# LPCB280_-_POWER.net
KiCad netlist of a schematic drawn in Altium Designer
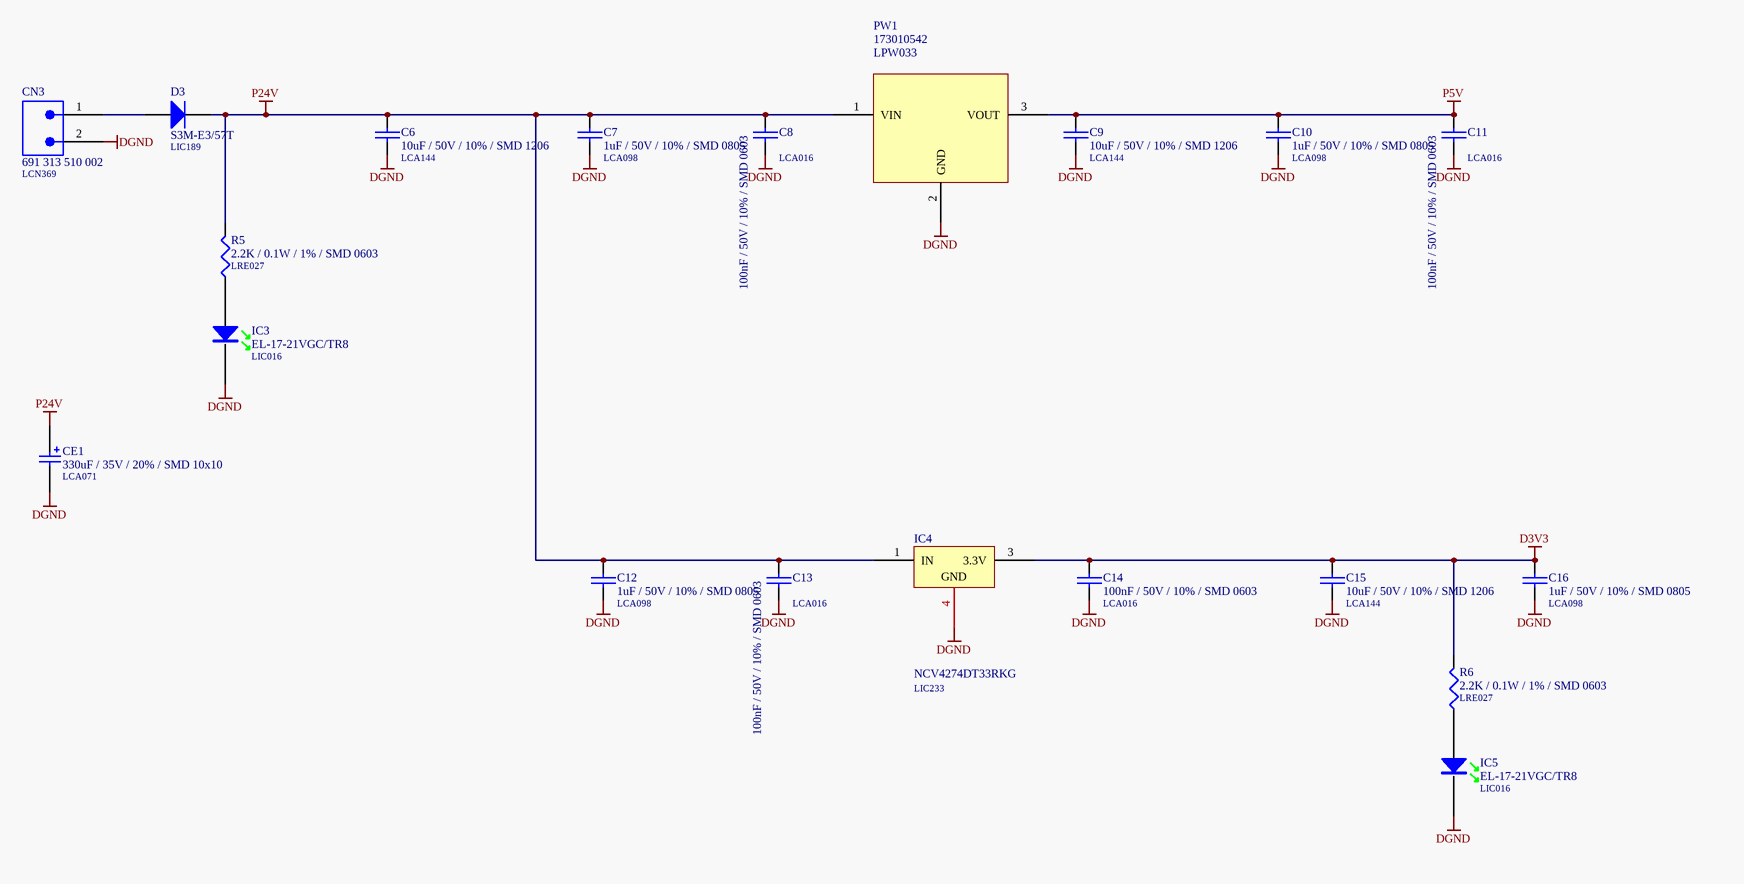
[diagram p0: LPCB280 - POWER.SchDoc]

(export (version "E")
  (design (tool "Eeschema 10.0.6"))
  (components
    (comp (ref "C6")
      (value "10uF / 50V / 10% / SMD 1206")
      (footprint "LFP043__CC3216-1206")
      (description "Capacitor, Ceramic Chip, 10uF, 50V, X5R, 10%, SMD 1206 [LCA144]")
      (fields (field (name "LDL_NUMBER") "LCA144"))
      (libsource (lib "LDL_Capacitors") (part "10uF / 50V / 10% / SMD 1206"))
    )
    (comp (ref "C7")
      (value "1uF / 50V / 10% / SMD 0805")
      (footprint "LFP010__CC2012-0805-IPC7351_B")
      (description "Capacitor, Ceramic Chip, 1uF, 50V, SMD 0805 [LCA098]")
      (fields (field (name "LDL_NUMBER") "LCA098"))
      (libsource (lib "LDL_Capacitors") (part "1uF / 50V / 10% / SMD 0805"))
    )
    (comp (ref "C8")
      (value "100nF / 50V / 10% / SMD 0603")
      (footprint "LFP011__CC1608-0603-IPC7351_B")
      (description "Capacitor, Ceramic Chip, 100nF (0.1uF), 50V, 5%, SMD 0603 [LCA016]")
      (fields (field (name "LDL_NUMBER") "LCA016"))
      (libsource (lib "LDL_Capacitors") (part "100nF / 50V / 10% / SMD 0603"))
    )
    (comp (ref "C9")
      (value "10uF / 50V / 10% / SMD 1206")
      (footprint "LFP043__CC3216-1206")
      (description "Capacitor, Ceramic Chip, 10uF, 50V, X5R, 10%, SMD 1206 [LCA144]")
      (fields (field (name "LDL_NUMBER") "LCA144"))
      (libsource (lib "LDL_Capacitors") (part "10uF / 50V / 10% / SMD 1206"))
    )
    (comp (ref "C10")
      (value "1uF / 50V / 10% / SMD 0805")
      (footprint "LFP010__CC2012-0805-IPC7351_B")
      (description "Capacitor, Ceramic Chip, 1uF, 50V, SMD 0805 [LCA098]")
      (fields (field (name "LDL_NUMBER") "LCA098"))
      (libsource (lib "LDL_Capacitors") (part "1uF / 50V / 10% / SMD 0805"))
    )
    (comp (ref "C11")
      (value "100nF / 50V / 10% / SMD 0603")
      (footprint "LFP011__CC1608-0603-IPC7351_B")
      (description "Capacitor, Ceramic Chip, 100nF (0.1uF), 50V, 5%, SMD 0603 [LCA016]")
      (fields (field (name "LDL_NUMBER") "LCA016"))
      (libsource (lib "LDL_Capacitors") (part "100nF / 50V / 10% / SMD 0603"))
    )
    (comp (ref "C12")
      (value "1uF / 50V / 10% / SMD 0805")
      (footprint "LFP010__CC2012-0805-IPC7351_B")
      (description "Capacitor, Ceramic Chip, 1uF, 50V, SMD 0805 [LCA098]")
      (fields (field (name "LDL_NUMBER") "LCA098"))
      (libsource (lib "LDL_Capacitors") (part "1uF / 50V / 10% / SMD 0805"))
    )
    (comp (ref "C13")
      (value "100nF / 50V / 10% / SMD 0603")
      (footprint "LFP011__CC1608-0603-IPC7351_B")
      (description "Capacitor, Ceramic Chip, 100nF (0.1uF), 50V, 5%, SMD 0603 [LCA016]")
      (fields (field (name "LDL_NUMBER") "LCA016"))
      (libsource (lib "LDL_Capacitors") (part "100nF / 50V / 10% / SMD 0603"))
    )
    (comp (ref "C14")
      (value "100nF / 50V / 10% / SMD 0603")
      (footprint "LFP011__CC1608-0603-IPC7351_B")
      (description "Capacitor, Ceramic Chip, 100nF (0.1uF), 50V, 5%, SMD 0603 [LCA016]")
      (fields (field (name "LDL_NUMBER") "LCA016"))
      (libsource (lib "LDL_Capacitors") (part "100nF / 50V / 10% / SMD 0603"))
    )
    (comp (ref "C15")
      (value "10uF / 50V / 10% / SMD 1206")
      (footprint "LFP043__CC3216-1206")
      (description "Capacitor, Ceramic Chip, 10uF, 50V, X5R, 10%, SMD 1206 [LCA144]")
      (fields (field (name "LDL_NUMBER") "LCA144"))
      (libsource (lib "LDL_Capacitors") (part "10uF / 50V / 10% / SMD 1206"))
    )
    (comp (ref "C16")
      (value "1uF / 50V / 10% / SMD 0805")
      (footprint "LFP010__CC2012-0805-IPC7351_B")
      (description "Capacitor, Ceramic Chip, 1uF, 50V, SMD 0805 [LCA098]")
      (fields (field (name "LDL_NUMBER") "LCA098"))
      (libsource (lib "LDL_Capacitors") (part "1uF / 50V / 10% / SMD 0805"))
    )
    (comp (ref "CE1")
      (value "330uF / 35V / 20% / SMD 10x10")
      (footprint "LFP041__NICHICON_WT_10X10")
      (description "Capacitor, Aluminum Electrolytic, 330uF, 35V, 20%, SMD (10mm x 10mm) [LCA071]")
      (fields (field (name "LDL_NUMBER") "LCA071"))
      (libsource (lib "LDL_Capacitors") (part "330uF / 35V / 20% / SMD 10x10"))
    )
    (comp (ref "CN3")
      (value "691 313 510 002")
      (footprint "691 313 510 002")
      (description "Connector, Pluggable Terminal Block, 5.08mm, 2 Way, PTH")
      (fields (field (name "LDL_NUMBER") "LCN369"))
      (libsource (lib "LDL_Connectors") (part "691 313 510 002"))
    )
    (comp (ref "D3")
      (value "S3M-E3/57T")
      (footprint "LFP040__DO-214AB")
      (description "Diode, General Purpose Rectifier, 3A, 200V, SMD DO-214AB [LIC189]")
      (fields (field (name "LDL_NUMBER") "LIC189"))
      (libsource (lib "LDL_Semiconductors") (part "S3M-E3/57T"))
    )
    (comp (ref "IC3")
      (value "EL-17-21VGC/TR8")
      (footprint "CR2012-0805-LED")
      (description "LED, SMD, 0805 Green [LIC016]")
      (fields (field (name "LDL_NUMBER") "LIC016"))
      (libsource (lib "LDL_Semiconductors") (part "EL-17-21VGC/TR8"))
    )
    (comp (ref "IC4")
      (value "NCV4274DT33RKG")
      (footprint "LFP019__369A-13")
      (description "IC, Voltage Regulator, 400mA, 3.3V LDO, SMD DPAK [LIC233]")
      (fields (field (name "LDL_NUMBER") "LIC233"))
      (libsource (lib "LDL_Semiconductors") (part "NCV4274DT33RKG"))
    )
    (comp (ref "IC5")
      (value "EL-17-21VGC/TR8")
      (footprint "CR2012-0805-LED")
      (description "LED, SMD, 0805 Green [LIC016]")
      (fields (field (name "LDL_NUMBER") "LIC016"))
      (libsource (lib "LDL_Semiconductors") (part "EL-17-21VGC/TR8"))
    )
    (comp (ref "PW1")
      (value "173010542")
      (footprint "173010542")
      (fields (field (name "LDL_NUMBER") "LPW033"))
      (libsource (lib "LDL_Power") (part "173010542"))
    )
    (comp (ref "R5")
      (value "2.2K / 0.1W / 1% / SMD 0603")
      (footprint "LFP020__CR1608-0603-IPC7351_B")
      (description "Resistor, Ceramic Chip, 2.2K, 0.1W, 1%, SMD 0603 [LRE027]")
      (fields (field (name "LDL_NUMBER") "LRE027"))
      (libsource (lib "LDL_Resistors") (part "2.2K / 0.1W / 1% / SMD 0603"))
    )
    (comp (ref "R6")
      (value "2.2K / 0.1W / 1% / SMD 0603")
      (footprint "LFP020__CR1608-0603-IPC7351_B")
      (description "Resistor, Ceramic Chip, 2.2K, 0.1W, 1%, SMD 0603 [LRE027]")
      (fields (field (name "LDL_NUMBER") "LRE027"))
      (libsource (lib "LDL_Resistors") (part "2.2K / 0.1W / 1% / SMD 0603"))
    )
  )
  (nets
    (net (code "1") (name "D3V3") (class "Default")
      (node (ref "C14") (pin "1") (pintype "passive"))
      (node (ref "C15") (pin "1") (pintype "passive"))
      (node (ref "C16") (pin "1") (pintype "passive"))
      (node (ref "IC4") (pin "3") (pinfunction "3.3V_3") (pintype "power_in"))
      (node (ref "R6") (pin "2") (pintype "passive"))
    )
    (net (code "2") (name "DGND") (class "Default")
      (node (ref "C10") (pin "2") (pintype "passive"))
      (node (ref "C11") (pin "2") (pintype "passive"))
      (node (ref "C12") (pin "2") (pintype "passive"))
      (node (ref "C13") (pin "2") (pintype "passive"))
      (node (ref "C14") (pin "2") (pintype "passive"))
      (node (ref "C15") (pin "2") (pintype "passive"))
      (node (ref "C16") (pin "2") (pintype "passive"))
      (node (ref "C6") (pin "2") (pintype "passive"))
      (node (ref "C7") (pin "2") (pintype "passive"))
      (node (ref "C8") (pin "2") (pintype "passive"))
      (node (ref "C9") (pin "2") (pintype "passive"))
      (node (ref "CE1") (pin "2") (pinfunction "2_2") (pintype "passive"))
      (node (ref "CN3") (pin "2") (pinfunction "2_2") (pintype "passive"))
      (node (ref "IC3") (pin "K") (pintype "passive"))
      (node (ref "IC4") (pin "4") (pinfunction "GND_4") (pintype "power_in"))
      (node (ref "IC5") (pin "K") (pintype "passive"))
      (node (ref "PW1") (pin "2") (pinfunction "GND_2") (pintype "passive"))
    )
    (net (code "3") (name "Net-(D3-A)") (class "Default")
      (node (ref "CN3") (pin "1") (pinfunction "1_1") (pintype "passive"))
      (node (ref "D3") (pin "2") (pinfunction "A_2") (pintype "passive"))
    )
    (net (code "4") (name "Net-(IC3-PadA)") (class "Default")
      (node (ref "IC3") (pin "A") (pintype "passive"))
      (node (ref "R5") (pin "1") (pintype "passive"))
    )
    (net (code "5") (name "Net-(IC5-PadA)") (class "Default")
      (node (ref "IC5") (pin "A") (pintype "passive"))
      (node (ref "R6") (pin "1") (pintype "passive"))
    )
    (net (code "6") (name "P5V") (class "Default")
      (node (ref "C10") (pin "1") (pintype "passive"))
      (node (ref "C11") (pin "1") (pintype "passive"))
      (node (ref "C9") (pin "1") (pintype "passive"))
      (node (ref "PW1") (pin "3") (pinfunction "VOUT_3") (pintype "passive"))
    )
    (net (code "7") (name "P24V") (class "Default")
      (node (ref "C12") (pin "1") (pintype "passive"))
      (node (ref "C13") (pin "1") (pintype "passive"))
      (node (ref "C6") (pin "1") (pintype "passive"))
      (node (ref "C7") (pin "1") (pintype "passive"))
      (node (ref "C8") (pin "1") (pintype "passive"))
      (node (ref "CE1") (pin "1") (pinfunction "1_1") (pintype "passive"))
      (node (ref "D3") (pin "1") (pinfunction "K_1") (pintype "passive"))
      (node (ref "IC4") (pin "1") (pinfunction "IN_1") (pintype "power_in"))
      (node (ref "PW1") (pin "1") (pinfunction "VIN_1") (pintype "passive"))
      (node (ref "R5") (pin "2") (pintype "passive"))
    )
  )
)
